# dcb_lite_adc.net
KiCad netlist of a schematic drawn in Altium Designer
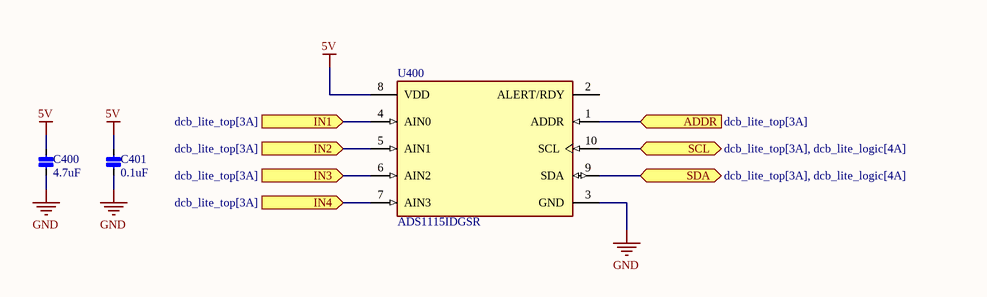
[diagram p0: dcb_lite_adc.SchDoc]

(export (version "E")
  (design (tool "Eeschema 10.0.6"))
  (components
    (comp (ref "C400")
      (value "4.7uF")
      (footprint "FP-CL10-IPC_C")
      (description "Cap Ceramic 4.7uF 6.3V X7R 10% SMD 0603 125°C Paper T/R")
      (fields (field (name "Comment") "CAP 4.7uF 0603 6.3V X7R"))
      (libsource (lib "StackFoundry LLC") (part "C-EU"))
    )
    (comp (ref "C401")
      (value "0.1uF")
      (footprint "FP-CL10-IPC_B")
      (description "Cap Ceramic 0.1uF 50V X7R 20% SMD 0603 125C Paper T/R")
      (fields (field (name "VOLTAGE") "50V") (field (name "Comment") "CAP 0.1uF 50V X7R 0603"))
      (libsource (lib "StackFoundry LLC") (part "C-EU"))
    )
    (comp (ref "U400")
      (value "ADS1115IDGSR")
      (footprint "FP-DGS0010A-IPC_A")
      (description "4-Channel Single ADC Delta-Sigma 860sps 16-bit Serial 10-Pin VSSOP T/R")
      (libsource (lib "StackFoundry LLC") (part "1442cd67780685bba1a77ae27c88037"))
    )
  )
  (nets
    (net (code "1") (name "/ADDR") (class "Default")
      (node (ref "U400") (pin "1") (pinfunction "ADDR_1") (pintype "input"))
    )
    (net (code "2") (name "/IN1") (class "Default")
      (node (ref "U400") (pin "4") (pinfunction "AIN0_4") (pintype "input"))
    )
    (net (code "3") (name "/IN2") (class "Default")
      (node (ref "U400") (pin "5") (pinfunction "AIN1_5") (pintype "input"))
    )
    (net (code "4") (name "/IN3") (class "Default")
      (node (ref "U400") (pin "6") (pinfunction "AIN2_6") (pintype "input"))
    )
    (net (code "5") (name "/IN4") (class "Default")
      (node (ref "U400") (pin "7") (pinfunction "AIN3_7") (pintype "input"))
    )
    (net (code "6") (name "/SCL") (class "Default")
      (node (ref "U400") (pin "10") (pinfunction "SCL_10") (pintype "input"))
    )
    (net (code "7") (name "/SDA") (class "Default")
      (node (ref "U400") (pin "9") (pinfunction "SDA_9") (pintype "bidirectional"))
    )
    (net (code "8") (name "5V") (class "Default")
      (node (ref "C400") (pin "1") (pinfunction "1_1") (pintype "passive"))
      (node (ref "C401") (pin "1") (pinfunction "1_1") (pintype "passive"))
      (node (ref "U400") (pin "8") (pinfunction "VDD_8") (pintype "power_in"))
    )
    (net (code "9") (name "GND") (class "Default")
      (node (ref "C400") (pin "2") (pinfunction "2_2") (pintype "passive"))
      (node (ref "C401") (pin "2") (pinfunction "2_2") (pintype "passive"))
      (node (ref "U400") (pin "3") (pinfunction "GND_3") (pintype "power_in"))
    )
    (net (code "10") (name "unconnected-(U400-ALERT{slash}RDY-Pad2)") (class "Default")
      (node (ref "U400") (pin "2") (pinfunction "ALERT/RDY_2") (pintype "open_collector"))
    )
  )
)
